# ESP.net
KiCad netlist of a schematic drawn in EAGLE
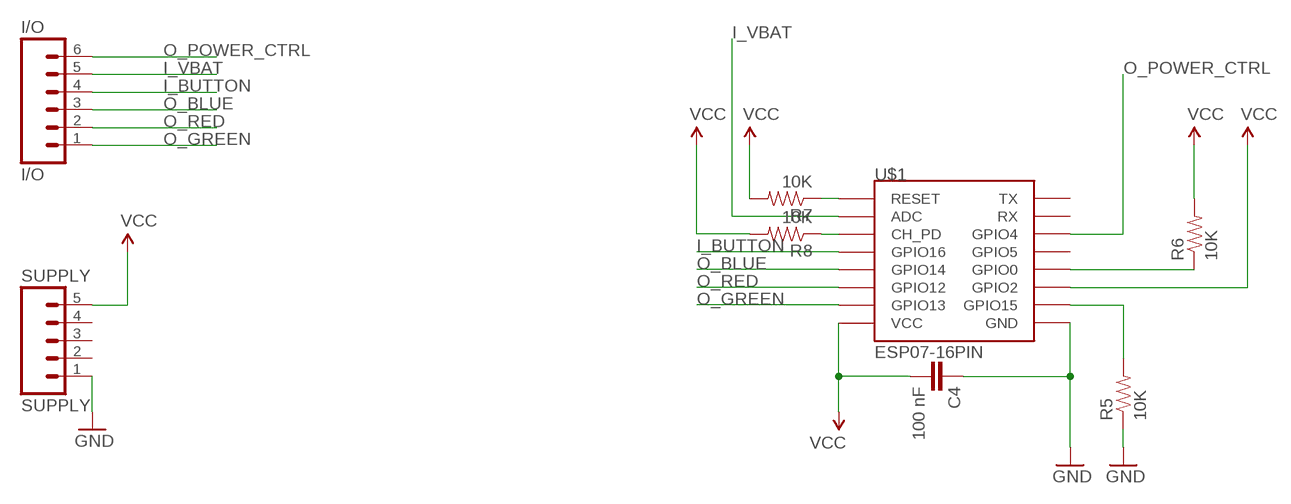
[diagram p0: schematic, sheet 1]

(export (version "E")
  (design (tool "Eeschema 10.0.6"))
  (components
    (comp (ref "C4")
      (value "100 nF")
      (footprint "eagle-import:0805")
      (libsource (lib "eagle-import") (part "CAP0805"))
    )
    (comp (ref "I/O")
      (value "I/O")
      (footprint "eagle-import:1X06_NO_SILK")
      (libsource (lib "eagle-import") (part "M06NO_SILK_FEMALE_PTH"))
    )
    (comp (ref "R5")
      (value "10K")
      (footprint "eagle-import:0805")
      (libsource (lib "eagle-import") (part "RESISTOR0805-RES"))
    )
    (comp (ref "R6")
      (value "10K")
      (footprint "eagle-import:0805")
      (libsource (lib "eagle-import") (part "RESISTOR0805-RES"))
    )
    (comp (ref "R7")
      (value "10K")
      (footprint "eagle-import:0805")
      (libsource (lib "eagle-import") (part "RESISTOR0805-RES"))
    )
    (comp (ref "R8")
      (value "10K")
      (footprint "eagle-import:0805")
      (libsource (lib "eagle-import") (part "RESISTOR0805-RES"))
    )
    (comp (ref "SUPPLY")
      (value "SUPPLY")
      (footprint "eagle-import:1X05_NO_SILK")
      (libsource (lib "eagle-import") (part "M05NO_SILK"))
    )
    (comp (ref "U$1")
      (value "ESP07-16PIN")
      (footprint "eagle-import:ESP07-16PIN")
      (libsource (lib "eagle-import") (part "ESP07-16PIN"))
    )
  )
  (nets
    (net (code "1") (name "/I_BUTTON") (class "Default")
      (node (ref "I/O") (pin "4") (pinfunction "4_4") (pintype "passive"))
      (node (ref "U$1") (pin "GPIO16") (pinfunction "GPIO16_GPIO16") (pintype "bidirectional"))
    )
    (net (code "2") (name "/I_VBAT") (class "Default")
      (node (ref "I/O") (pin "5") (pinfunction "5_5") (pintype "passive"))
      (node (ref "U$1") (pin "ADC") (pinfunction "ADC_ADC") (pintype "bidirectional"))
    )
    (net (code "3") (name "/O_BLUE") (class "Default")
      (node (ref "I/O") (pin "3") (pinfunction "3_3") (pintype "passive"))
      (node (ref "U$1") (pin "GPIO14") (pinfunction "GPIO14_GPIO14") (pintype "bidirectional"))
    )
    (net (code "4") (name "/O_GREEN") (class "Default")
      (node (ref "I/O") (pin "1") (pinfunction "1_1") (pintype "passive"))
      (node (ref "U$1") (pin "GPIO13") (pinfunction "GPIO13_GPIO13") (pintype "bidirectional"))
    )
    (net (code "5") (name "/O_POWER_CTRL") (class "Default")
      (node (ref "I/O") (pin "6") (pinfunction "6_6") (pintype "passive"))
      (node (ref "U$1") (pin "GPIO4") (pinfunction "GPIO4_GPIO4") (pintype "bidirectional"))
    )
    (net (code "6") (name "/O_RED") (class "Default")
      (node (ref "I/O") (pin "2") (pinfunction "2_2") (pintype "passive"))
      (node (ref "U$1") (pin "GPIO12") (pinfunction "GPIO12_GPIO12") (pintype "bidirectional"))
    )
    (net (code "7") (name "GND") (class "Default")
      (node (ref "C4") (pin "1") (pinfunction "1_1") (pintype "passive"))
      (node (ref "R5") (pin "1") (pinfunction "1_1") (pintype "passive"))
      (node (ref "SUPPLY") (pin "1") (pinfunction "1_1") (pintype "passive"))
      (node (ref "U$1") (pin "GND") (pinfunction "GND_GND") (pintype "bidirectional"))
    )
    (net (code "8") (name "Net-(R5-Pad2)") (class "Default")
      (node (ref "R5") (pin "2") (pinfunction "2_2") (pintype "passive"))
      (node (ref "U$1") (pin "GPIO15") (pinfunction "GPIO15_GPIO15") (pintype "bidirectional"))
    )
    (net (code "9") (name "Net-(R6-Pad1)") (class "Default")
      (node (ref "R6") (pin "1") (pinfunction "1_1") (pintype "passive"))
      (node (ref "U$1") (pin "GPIO0") (pinfunction "GPIO0_GPIO0") (pintype "bidirectional"))
    )
    (net (code "10") (name "Net-(R8-Pad1)") (class "Default")
      (node (ref "R8") (pin "1") (pinfunction "1_1") (pintype "passive"))
      (node (ref "U$1") (pin "CH_PD") (pinfunction "CH_PD_CH_PD") (pintype "bidirectional"))
    )
    (net (code "11") (name "Net-(U$1-RESET)") (class "Default")
      (node (ref "R7") (pin "1") (pinfunction "1_1") (pintype "passive"))
      (node (ref "U$1") (pin "REST") (pinfunction "RESET_REST") (pintype "bidirectional"))
    )
    (net (code "12") (name "VCC") (class "Default")
      (node (ref "C4") (pin "2") (pinfunction "2_2") (pintype "passive"))
      (node (ref "R6") (pin "2") (pinfunction "2_2") (pintype "passive"))
      (node (ref "R7") (pin "2") (pinfunction "2_2") (pintype "passive"))
      (node (ref "R8") (pin "2") (pinfunction "2_2") (pintype "passive"))
      (node (ref "SUPPLY") (pin "5") (pinfunction "5_5") (pintype "passive"))
      (node (ref "U$1") (pin "GPIO2") (pinfunction "GPIO2_GPIO2") (pintype "bidirectional"))
      (node (ref "U$1") (pin "VCC") (pinfunction "VCC_VCC") (pintype "bidirectional"))
    )
    (net (code "13") (name "unconnected-(SUPPLY-Pad2)") (class "Default")
      (node (ref "SUPPLY") (pin "2") (pinfunction "2_2") (pintype "passive"))
    )
    (net (code "14") (name "unconnected-(SUPPLY-Pad3)") (class "Default")
      (node (ref "SUPPLY") (pin "3") (pinfunction "3_3") (pintype "passive"))
    )
    (net (code "15") (name "unconnected-(SUPPLY-Pad4)") (class "Default")
      (node (ref "SUPPLY") (pin "4") (pinfunction "4_4") (pintype "passive"))
    )
    (net (code "16") (name "unconnected-(U$1-PadGPIO5)") (class "Default")
      (node (ref "U$1") (pin "GPIO5") (pinfunction "GPIO5_GPIO5") (pintype "bidirectional"))
    )
    (net (code "17") (name "unconnected-(U$1-PadRX)") (class "Default")
      (node (ref "U$1") (pin "RX") (pinfunction "RX_RX") (pintype "bidirectional"))
    )
    (net (code "18") (name "unconnected-(U$1-PadTX)") (class "Default")
      (node (ref "U$1") (pin "TX") (pinfunction "TX_TX") (pintype "bidirectional"))
    )
  )
)
